# keyboard.net
KiCad netlist of a schematic drawn in Altium Designer
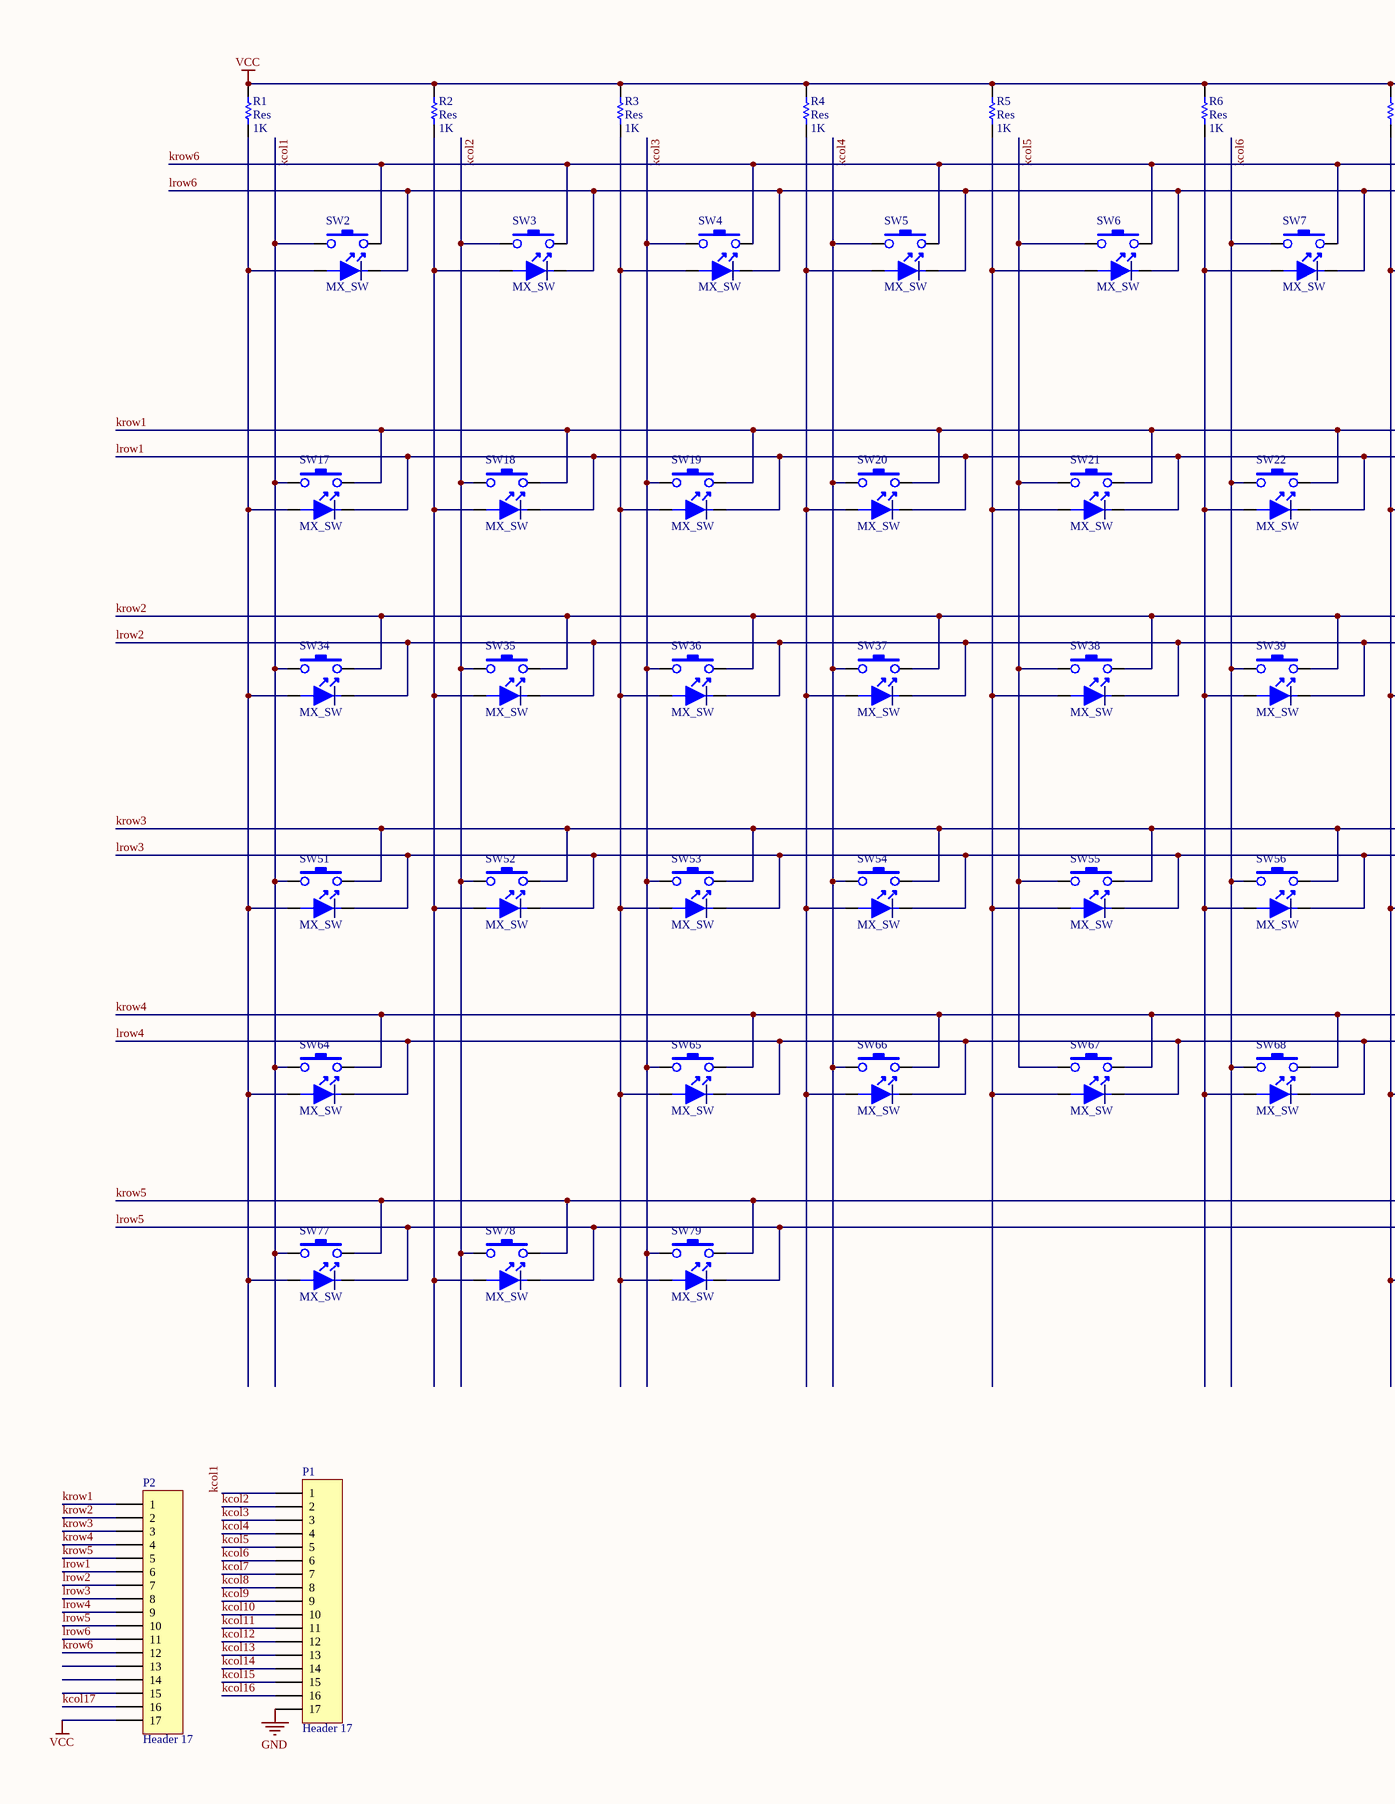
[diagram p0: keyboard.SchDoc, left]
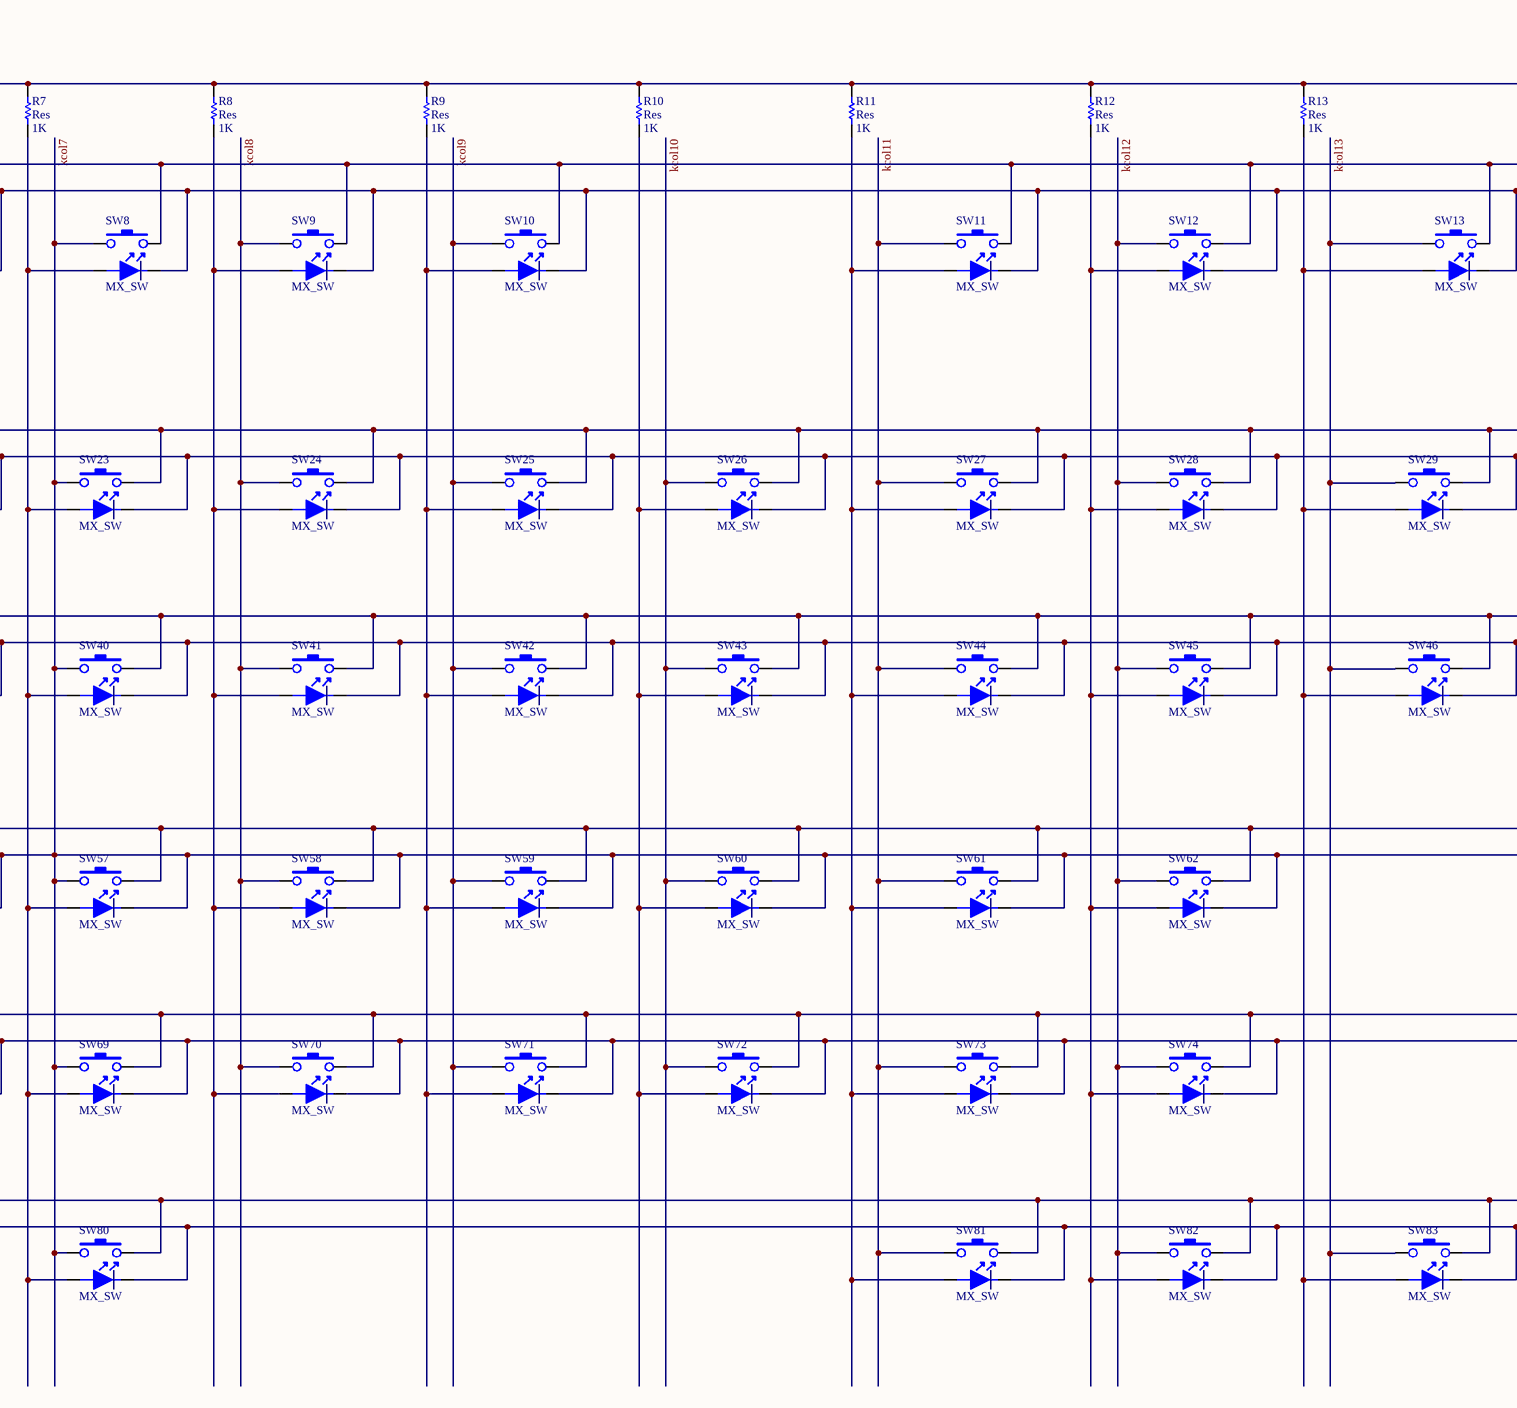
[diagram p1: keyboard.SchDoc, middle]
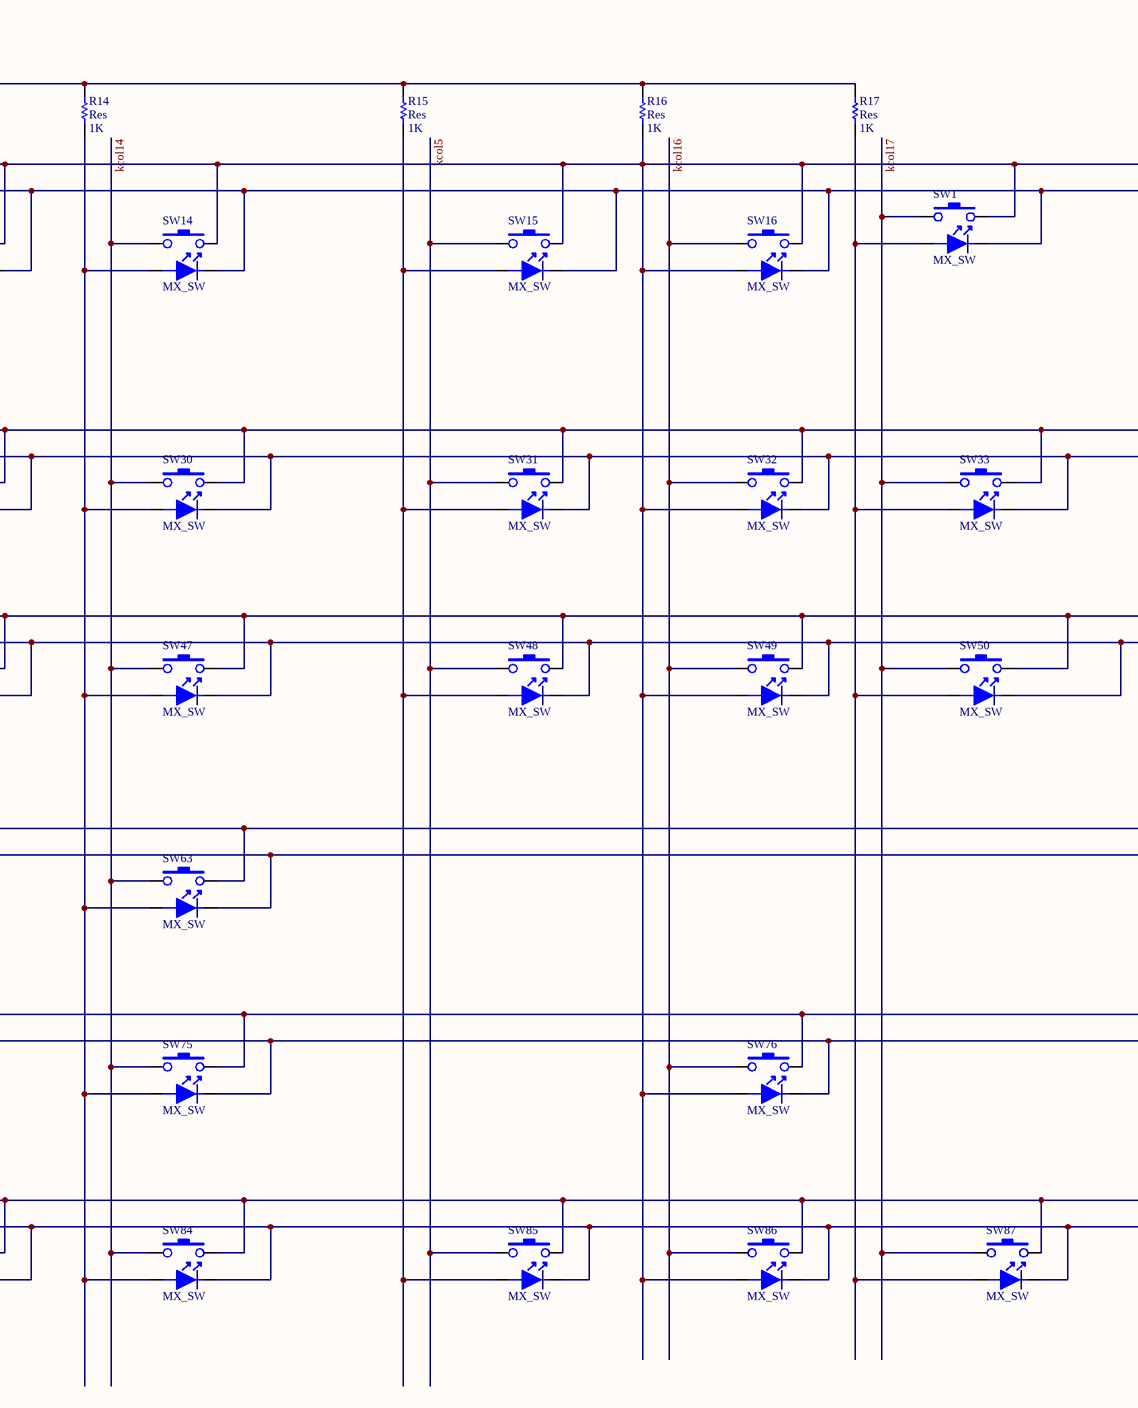
[diagram p2: keyboard.SchDoc, right]

(export (version "E")
  (design (tool "Eeschema 10.0.6"))
  (components
    (comp (ref "P1")
      (value "Header 17")
      (footprint "HDR1X17")
      (description "Header, 17-Pin")
      (fields (field (name "PUBLISHER") "Altium Limited"))
      (libsource (lib "常用元件集成库") (part "Header 17"))
    )
    (comp (ref "P2")
      (value "Header 17")
      (footprint "HDR1X17")
      (description "Header, 17-Pin")
      (fields (field (name "PUBLISHER") "Altium Limited"))
      (libsource (lib "常用元件集成库") (part "Header 17"))
    )
    (comp (ref "R1")
      (value "Res")
      (footprint "R2012")
      (description "贴片电阻")
      (fields (field (name "ALTIUM_VALUE") "1K") (field (name "PUBLISHER") "Altium Limited"))
      (libsource (lib "常用元件集成库") (part "Res"))
    )
    (comp (ref "R2")
      (value "Res")
      (footprint "R2012")
      (description "贴片电阻")
      (fields (field (name "ALTIUM_VALUE") "1K") (field (name "PUBLISHER") "Altium Limited"))
      (libsource (lib "常用元件集成库") (part "Res"))
    )
    (comp (ref "R3")
      (value "Res")
      (footprint "R2012")
      (description "贴片电阻")
      (fields (field (name "ALTIUM_VALUE") "1K") (field (name "PUBLISHER") "Altium Limited"))
      (libsource (lib "常用元件集成库") (part "Res"))
    )
    (comp (ref "R4")
      (value "Res")
      (footprint "R2012")
      (description "贴片电阻")
      (fields (field (name "ALTIUM_VALUE") "1K") (field (name "PUBLISHER") "Altium Limited"))
      (libsource (lib "常用元件集成库") (part "Res"))
    )
    (comp (ref "R5")
      (value "Res")
      (footprint "R2012")
      (description "贴片电阻")
      (fields (field (name "ALTIUM_VALUE") "1K") (field (name "PUBLISHER") "Altium Limited"))
      (libsource (lib "常用元件集成库") (part "Res"))
    )
    (comp (ref "R6")
      (value "Res")
      (footprint "R2012")
      (description "贴片电阻")
      (fields (field (name "ALTIUM_VALUE") "1K") (field (name "PUBLISHER") "Altium Limited"))
      (libsource (lib "常用元件集成库") (part "Res"))
    )
    (comp (ref "R7")
      (value "Res")
      (footprint "R2012")
      (description "贴片电阻")
      (fields (field (name "ALTIUM_VALUE") "1K") (field (name "PUBLISHER") "Altium Limited"))
      (libsource (lib "常用元件集成库") (part "Res"))
    )
    (comp (ref "R8")
      (value "Res")
      (footprint "R2012")
      (description "贴片电阻")
      (fields (field (name "ALTIUM_VALUE") "1K") (field (name "PUBLISHER") "Altium Limited"))
      (libsource (lib "常用元件集成库") (part "Res"))
    )
    (comp (ref "R9")
      (value "Res")
      (footprint "R2012")
      (description "贴片电阻")
      (fields (field (name "ALTIUM_VALUE") "1K") (field (name "PUBLISHER") "Altium Limited"))
      (libsource (lib "常用元件集成库") (part "Res"))
    )
    (comp (ref "R10")
      (value "Res")
      (footprint "R2012")
      (description "贴片电阻")
      (fields (field (name "ALTIUM_VALUE") "1K") (field (name "PUBLISHER") "Altium Limited"))
      (libsource (lib "常用元件集成库") (part "Res"))
    )
    (comp (ref "R11")
      (value "Res")
      (footprint "R2012")
      (description "贴片电阻")
      (fields (field (name "ALTIUM_VALUE") "1K") (field (name "PUBLISHER") "Altium Limited"))
      (libsource (lib "常用元件集成库") (part "Res"))
    )
    (comp (ref "R12")
      (value "Res")
      (footprint "R2012")
      (description "贴片电阻")
      (fields (field (name "ALTIUM_VALUE") "1K") (field (name "PUBLISHER") "Altium Limited"))
      (libsource (lib "常用元件集成库") (part "Res"))
    )
    (comp (ref "R13")
      (value "Res")
      (footprint "R2012")
      (description "贴片电阻")
      (fields (field (name "ALTIUM_VALUE") "1K") (field (name "PUBLISHER") "Altium Limited"))
      (libsource (lib "常用元件集成库") (part "Res"))
    )
    (comp (ref "R14")
      (value "Res")
      (footprint "R2012")
      (description "贴片电阻")
      (fields (field (name "ALTIUM_VALUE") "1K") (field (name "PUBLISHER") "Altium Limited"))
      (libsource (lib "常用元件集成库") (part "Res"))
    )
    (comp (ref "R15")
      (value "Res")
      (footprint "R2012")
      (description "贴片电阻")
      (fields (field (name "ALTIUM_VALUE") "1K") (field (name "PUBLISHER") "Altium Limited"))
      (libsource (lib "常用元件集成库") (part "Res"))
    )
    (comp (ref "R16")
      (value "Res")
      (footprint "R2012")
      (description "贴片电阻")
      (fields (field (name "ALTIUM_VALUE") "1K") (field (name "PUBLISHER") "Altium Limited"))
      (libsource (lib "常用元件集成库") (part "Res"))
    )
    (comp (ref "R17")
      (value "Res")
      (footprint "R2012")
      (description "贴片电阻")
      (fields (field (name "ALTIUM_VALUE") "1K") (field (name "PUBLISHER") "Altium Limited"))
      (libsource (lib "常用元件集成库") (part "Res"))
    )
    (comp (ref "SW1")
      (value "MX_SW")
      (footprint "MX_SW-2")
      (description "without Fixation pins  1-Pole w/LED")
      (libsource (lib "KeyBoard") (part "MX_SW-2"))
    )
    (comp (ref "SW2")
      (value "MX_SW")
      (footprint "MX_SW-2")
      (description "without Fixation pins  1-Pole w/LED")
      (libsource (lib "KeyBoard") (part "MX_SW-2"))
    )
    (comp (ref "SW3")
      (value "MX_SW")
      (footprint "MX_SW-2")
      (description "without Fixation pins  1-Pole w/LED")
      (libsource (lib "KeyBoard") (part "MX_SW-2"))
    )
    (comp (ref "SW4")
      (value "MX_SW")
      (footprint "MX_SW-2")
      (description "without Fixation pins  1-Pole w/LED")
      (libsource (lib "KeyBoard") (part "MX_SW-2"))
    )
    (comp (ref "SW5")
      (value "MX_SW")
      (footprint "MX_SW-2")
      (description "without Fixation pins  1-Pole w/LED")
      (libsource (lib "KeyBoard") (part "MX_SW-2"))
    )
    (comp (ref "SW6")
      (value "MX_SW")
      (footprint "MX_SW-2")
      (description "without Fixation pins  1-Pole w/LED")
      (libsource (lib "KeyBoard") (part "MX_SW-2"))
    )
    (comp (ref "SW7")
      (value "MX_SW")
      (footprint "MX_SW-2")
      (description "without Fixation pins  1-Pole w/LED")
      (libsource (lib "KeyBoard") (part "MX_SW-2"))
    )
    (comp (ref "SW8")
      (value "MX_SW")
      (footprint "MX_SW-2")
      (description "without Fixation pins  1-Pole w/LED")
      (libsource (lib "KeyBoard") (part "MX_SW-2"))
    )
    (comp (ref "SW9")
      (value "MX_SW")
      (footprint "MX_SW-2")
      (description "without Fixation pins  1-Pole w/LED")
      (libsource (lib "KeyBoard") (part "MX_SW-2"))
    )
    (comp (ref "SW10")
      (value "MX_SW")
      (footprint "MX_SW-2")
      (description "without Fixation pins  1-Pole w/LED")
      (libsource (lib "KeyBoard") (part "MX_SW-2"))
    )
    (comp (ref "SW11")
      (value "MX_SW")
      (footprint "MX_SW-2")
      (description "without Fixation pins  1-Pole w/LED")
      (libsource (lib "KeyBoard") (part "MX_SW-2"))
    )
    (comp (ref "SW12")
      (value "MX_SW")
      (footprint "MX_SW-2")
      (description "without Fixation pins  1-Pole w/LED")
      (libsource (lib "KeyBoard") (part "MX_SW-2"))
    )
    (comp (ref "SW13")
      (value "MX_SW")
      (footprint "MX_SW-2")
      (description "without Fixation pins  1-Pole w/LED")
      (libsource (lib "KeyBoard") (part "MX_SW-2"))
    )
    (comp (ref "SW14")
      (value "MX_SW")
      (footprint "MX_SW-2")
      (description "without Fixation pins  1-Pole w/LED")
      (libsource (lib "KeyBoard") (part "MX_SW-2"))
    )
    (comp (ref "SW15")
      (value "MX_SW")
      (footprint "MX_SW-2")
      (description "without Fixation pins  1-Pole w/LED")
      (libsource (lib "KeyBoard") (part "MX_SW-2"))
    )
    (comp (ref "SW16")
      (value "MX_SW")
      (footprint "MX_SW-2")
      (description "without Fixation pins  1-Pole w/LED")
      (libsource (lib "KeyBoard") (part "MX_SW-2"))
    )
    (comp (ref "SW17")
      (value "MX_SW")
      (footprint "MX_SW-2")
      (description "without Fixation pins  1-Pole w/LED")
      (libsource (lib "KeyBoard") (part "MX_SW-2"))
    )
    (comp (ref "SW18")
      (value "MX_SW")
      (footprint "MX_SW-2")
      (description "without Fixation pins  1-Pole w/LED")
      (libsource (lib "KeyBoard") (part "MX_SW-2"))
    )
    (comp (ref "SW19")
      (value "MX_SW")
      (footprint "MX_SW-2")
      (description "without Fixation pins  1-Pole w/LED")
      (libsource (lib "KeyBoard") (part "MX_SW-2"))
    )
    (comp (ref "SW20")
      (value "MX_SW")
      (footprint "MX_SW-2")
      (description "without Fixation pins  1-Pole w/LED")
      (libsource (lib "KeyBoard") (part "MX_SW-2"))
    )
    (comp (ref "SW21")
      (value "MX_SW")
      (footprint "MX_SW-2")
      (description "without Fixation pins  1-Pole w/LED")
      (libsource (lib "KeyBoard") (part "MX_SW-2"))
    )
    (comp (ref "SW22")
      (value "MX_SW")
      (footprint "MX_SW-2")
      (description "without Fixation pins  1-Pole w/LED")
      (libsource (lib "KeyBoard") (part "MX_SW-2"))
    )
    (comp (ref "SW23")
      (value "MX_SW")
      (footprint "MX_SW-2")
      (description "without Fixation pins  1-Pole w/LED")
      (libsource (lib "KeyBoard") (part "MX_SW-2"))
    )
    (comp (ref "SW24")
      (value "MX_SW")
      (footprint "MX_SW-2")
      (description "without Fixation pins  1-Pole w/LED")
      (libsource (lib "KeyBoard") (part "MX_SW-2"))
    )
    (comp (ref "SW25")
      (value "MX_SW")
      (footprint "MX_SW-2")
      (description "without Fixation pins  1-Pole w/LED")
      (libsource (lib "KeyBoard") (part "MX_SW-2"))
    )
    (comp (ref "SW26")
      (value "MX_SW")
      (footprint "MX_SW-2")
      (description "without Fixation pins  1-Pole w/LED")
      (libsource (lib "KeyBoard") (part "MX_SW-2"))
    )
    (comp (ref "SW27")
      (value "MX_SW")
      (footprint "MX_SW-2")
      (description "without Fixation pins  1-Pole w/LED")
      (libsource (lib "KeyBoard") (part "MX_SW-2"))
    )
    (comp (ref "SW28")
      (value "MX_SW")
      (footprint "MX_SW-2")
      (description "without Fixation pins  1-Pole w/LED")
      (libsource (lib "KeyBoard") (part "MX_SW-2"))
    )
    (comp (ref "SW29")
      (value "MX_SW")
      (footprint "MX_SW-2")
      (description "without Fixation pins  1-Pole w/LED")
      (libsource (lib "KeyBoard") (part "MX_SW-2"))
    )
    (comp (ref "SW30")
      (value "MX_SW")
      (footprint "MX_SW-2")
      (description "without Fixation pins  1-Pole w/LED")
      (libsource (lib "KeyBoard") (part "MX_SW-2"))
    )
    (comp (ref "SW31")
      (value "MX_SW")
      (footprint "MX_SW-2")
      (description "without Fixation pins  1-Pole w/LED")
      (libsource (lib "KeyBoard") (part "MX_SW-2"))
    )
    (comp (ref "SW32")
      (value "MX_SW")
      (footprint "MX_SW-2")
      (description "without Fixation pins  1-Pole w/LED")
      (libsource (lib "KeyBoard") (part "MX_SW-2"))
    )
    (comp (ref "SW33")
      (value "MX_SW")
      (footprint "MX_SW-2")
      (description "without Fixation pins  1-Pole w/LED")
      (libsource (lib "KeyBoard") (part "MX_SW-2"))
    )
    (comp (ref "SW34")
      (value "MX_SW")
      (footprint "MX_SW-2")
      (description "without Fixation pins  1-Pole w/LED")
      (libsource (lib "KeyBoard") (part "MX_SW-2"))
    )
    (comp (ref "SW35")
      (value "MX_SW")
      (footprint "MX_SW-2")
      (description "without Fixation pins  1-Pole w/LED")
      (libsource (lib "KeyBoard") (part "MX_SW-2"))
    )
    (comp (ref "SW36")
      (value "MX_SW")
      (footprint "MX_SW-2")
      (description "without Fixation pins  1-Pole w/LED")
      (libsource (lib "KeyBoard") (part "MX_SW-2"))
    )
    (comp (ref "SW37")
      (value "MX_SW")
      (footprint "MX_SW-2")
      (description "without Fixation pins  1-Pole w/LED")
      (libsource (lib "KeyBoard") (part "MX_SW-2"))
    )
    (comp (ref "SW38")
      (value "MX_SW")
      (footprint "MX_SW-2")
      (description "without Fixation pins  1-Pole w/LED")
      (libsource (lib "KeyBoard") (part "MX_SW-2"))
    )
    (comp (ref "SW39")
      (value "MX_SW")
      (footprint "MX_SW-2")
      (description "without Fixation pins  1-Pole w/LED")
      (libsource (lib "KeyBoard") (part "MX_SW-2"))
    )
    (comp (ref "SW40")
      (value "MX_SW")
      (footprint "MX_SW-2")
      (description "without Fixation pins  1-Pole w/LED")
      (libsource (lib "KeyBoard") (part "MX_SW-2"))
    )
    (comp (ref "SW41")
      (value "MX_SW")
      (footprint "MX_SW-2")
      (description "without Fixation pins  1-Pole w/LED")
      (libsource (lib "KeyBoard") (part "MX_SW-2"))
    )
    (comp (ref "SW42")
      (value "MX_SW")
      (footprint "MX_SW-2")
      (description "without Fixation pins  1-Pole w/LED")
      (libsource (lib "KeyBoard") (part "MX_SW-2"))
    )
    (comp (ref "SW43")
      (value "MX_SW")
      (footprint "MX_SW-2")
      (description "without Fixation pins  1-Pole w/LED")
      (libsource (lib "KeyBoard") (part "MX_SW-2"))
    )
    (comp (ref "SW44")
      (value "MX_SW")
      (footprint "MX_SW-2")
      (description "without Fixation pins  1-Pole w/LED")
      (libsource (lib "KeyBoard") (part "MX_SW-2"))
    )
    (comp (ref "SW45")
      (value "MX_SW")
      (footprint "MX_SW-2")
      (description "without Fixation pins  1-Pole w/LED")
      (libsource (lib "KeyBoard") (part "MX_SW-2"))
    )
    (comp (ref "SW46")
      (value "MX_SW")
      (footprint "MX_SW-2")
      (description "without Fixation pins  1-Pole w/LED")
      (libsource (lib "KeyBoard") (part "MX_SW-2"))
    )
    (comp (ref "SW47")
      (value "MX_SW")
      (footprint "MX_SW-2")
      (description "without Fixation pins  1-Pole w/LED")
      (libsource (lib "KeyBoard") (part "MX_SW-2"))
    )
    (comp (ref "SW48")
      (value "MX_SW")
      (footprint "MX_SW-2")
      (description "without Fixation pins  1-Pole w/LED")
      (libsource (lib "KeyBoard") (part "MX_SW-2"))
    )
    (comp (ref "SW49")
      (value "MX_SW")
      (footprint "MX_SW-2")
      (description "without Fixation pins  1-Pole w/LED")
      (libsource (lib "KeyBoard") (part "MX_SW-2"))
    )
    (comp (ref "SW50")
      (value "MX_SW")
      (footprint "MX_SW-2")
      (description "without Fixation pins  1-Pole w/LED")
      (libsource (lib "KeyBoard") (part "MX_SW-2"))
    )
    (comp (ref "SW51")
      (value "MX_SW")
      (footprint "MX_SW-2")
      (description "without Fixation pins  1-Pole w/LED")
      (libsource (lib "KeyBoard") (part "MX_SW-2"))
    )
    (comp (ref "SW52")
      (value "MX_SW")
      (footprint "MX_SW-2")
      (description "without Fixation pins  1-Pole w/LED")
      (libsource (lib "KeyBoard") (part "MX_SW-2"))
    )
    (comp (ref "SW53")
      (value "MX_SW")
      (footprint "MX_SW-2")
      (description "without Fixation pins  1-Pole w/LED")
      (libsource (lib "KeyBoard") (part "MX_SW-2"))
    )
    (comp (ref "SW54")
      (value "MX_SW")
      (footprint "MX_SW-2")
      (description "without Fixation pins  1-Pole w/LED")
      (libsource (lib "KeyBoard") (part "MX_SW-2"))
    )
    (comp (ref "SW55")
      (value "MX_SW")
      (footprint "MX_SW-2")
      (description "without Fixation pins  1-Pole w/LED")
      (libsource (lib "KeyBoard") (part "MX_SW-2"))
    )
    (comp (ref "SW56")
      (value "MX_SW")
      (footprint "MX_SW-2")
      (description "without Fixation pins  1-Pole w/LED")
      (libsource (lib "KeyBoard") (part "MX_SW-2"))
    )
    (comp (ref "SW57")
      (value "MX_SW")
      (footprint "MX_SW-2")
      (description "without Fixation pins  1-Pole w/LED")
      (libsource (lib "KeyBoard") (part "MX_SW-2"))
    )
    (comp (ref "SW58")
      (value "MX_SW")
      (footprint "MX_SW-2")
      (description "without Fixation pins  1-Pole w/LED")
      (libsource (lib "KeyBoard") (part "MX_SW-2"))
    )
    (comp (ref "SW59")
      (value "MX_SW")
      (footprint "MX_SW-2")
      (description "without Fixation pins  1-Pole w/LED")
      (libsource (lib "KeyBoard") (part "MX_SW-2"))
    )
    (comp (ref "SW60")
      (value "MX_SW")
      (footprint "MX_SW-2")
      (description "without Fixation pins  1-Pole w/LED")
      (libsource (lib "KeyBoard") (part "MX_SW-2"))
    )
    (comp (ref "SW61")
      (value "MX_SW")
      (footprint "MX_SW-2")
      (description "without Fixation pins  1-Pole w/LED")
      (libsource (lib "KeyBoard") (part "MX_SW-2"))
    )
    (comp (ref "SW62")
      (value "MX_SW")
      (footprint "MX_SW-2")
      (description "without Fixation pins  1-Pole w/LED")
      (libsource (lib "KeyBoard") (part "MX_SW-2"))
    )
    (comp (ref "SW63")
      (value "MX_SW")
      (footprint "MX_SW-2")
      (description "without Fixation pins  1-Pole w/LED")
      (libsource (lib "KeyBoard") (part "MX_SW-2"))
    )
    (comp (ref "SW64")
      (value "MX_SW")
      (footprint "MX_SW-2")
      (description "without Fixation pins  1-Pole w/LED")
      (libsource (lib "KeyBoard") (part "MX_SW-2"))
    )
    (comp (ref "SW65")
      (value "MX_SW")
      (footprint "MX_SW-2")
      (description "without Fixation pins  1-Pole w/LED")
      (libsource (lib "KeyBoard") (part "MX_SW-2"))
    )
    (comp (ref "SW66")
      (value "MX_SW")
      (footprint "MX_SW-2")
      (description "without Fixation pins  1-Pole w/LED")
      (libsource (lib "KeyBoard") (part "MX_SW-2"))
    )
    (comp (ref "SW67")
      (value "MX_SW")
      (footprint "MX_SW-2")
      (description "without Fixation pins  1-Pole w/LED")
      (libsource (lib "KeyBoard") (part "MX_SW-2"))
    )
    (comp (ref "SW68")
      (value "MX_SW")
      (footprint "MX_SW-2")
      (description "without Fixation pins  1-Pole w/LED")
      (libsource (lib "KeyBoard") (part "MX_SW-2"))
    )
    (comp (ref "SW69")
      (value "MX_SW")
      (footprint "MX_SW-2")
      (description "without Fixation pins  1-Pole w/LED")
      (libsource (lib "KeyBoard") (part "MX_SW-2"))
    )
    (comp (ref "SW70")
      (value "MX_SW")
      (footprint "MX_SW-2")
      (description "without Fixation pins  1-Pole w/LED")
      (libsource (lib "KeyBoard") (part "MX_SW-2"))
    )
    (comp (ref "SW71")
      (value "MX_SW")
      (footprint "MX_SW-2")
      (description "without Fixation pins  1-Pole w/LED")
      (libsource (lib "KeyBoard") (part "MX_SW-2"))
    )
    (comp (ref "SW72")
      (value "MX_SW")
      (footprint "MX_SW-2")
      (description "without Fixation pins  1-Pole w/LED")
      (libsource (lib "KeyBoard") (part "MX_SW-2"))
    )
    (comp (ref "SW73")
      (value "MX_SW")
      (footprint "MX_SW-2")
      (description "without Fixation pins  1-Pole w/LED")
      (libsource (lib "KeyBoard") (part "MX_SW-2"))
    )
    (comp (ref "SW74")
      (value "MX_SW")
      (footprint "MX_SW-2")
      (description "without Fixation pins  1-Pole w/LED")
      (libsource (lib "KeyBoard") (part "MX_SW-2"))
    )
    (comp (ref "SW75")
      (value "MX_SW")
      (footprint "MX_SW-2")
      (description "without Fixation pins  1-Pole w/LED")
      (libsource (lib "KeyBoard") (part "MX_SW-2"))
    )
    (comp (ref "SW76")
      (value "MX_SW")
      (footprint "MX_SW-2")
      (description "without Fixation pins  1-Pole w/LED")
      (libsource (lib "KeyBoard") (part "MX_SW-2"))
    )
    (comp (ref "SW77")
      (value "MX_SW")
      (footprint "MX_SW-2")
      (description "without Fixation pins  1-Pole w/LED")
      (libsource (lib "KeyBoard") (part "MX_SW-2"))
    )
    (comp (ref "SW78")
      (value "MX_SW")
      (footprint "MX_SW-2")
      (description "without Fixation pins  1-Pole w/LED")
      (libsource (lib "KeyBoard") (part "MX_SW-2"))
    )
    (comp (ref "SW79")
      (value "MX_SW")
      (footprint "MX_SW-2")
      (description "without Fixation pins  1-Pole w/LED")
      (libsource (lib "KeyBoard") (part "MX_SW-2"))
    )
    (comp (ref "SW80")
      (value "MX_SW")
      (footprint "MX_SW-2")
      (description "without Fixation pins  1-Pole w/LED")
      (libsource (lib "KeyBoard") (part "MX_SW-2"))
    )
    (comp (ref "SW81")
      (value "MX_SW")
      (footprint "MX_SW-2")
      (description "without Fixation pins  1-Pole w/LED")
      (libsource (lib "KeyBoard") (part "MX_SW-2"))
    )
    (comp (ref "SW82")
      (value "MX_SW")
      (footprint "MX_SW-2")
      (description "without Fixation pins  1-Pole w/LED")
      (libsource (lib "KeyBoard") (part "MX_SW-2"))
    )
    (comp (ref "SW83")
      (value "MX_SW")
      (footprint "MX_SW-2")
      (description "without Fixation pins  1-Pole w/LED")
      (libsource (lib "KeyBoard") (part "MX_SW-2"))
    )
    (comp (ref "SW84")
      (value "MX_SW")
      (footprint "MX_SW-2")
      (description "without Fixation pins  1-Pole w/LED")
      (libsource (lib "KeyBoard") (part "MX_SW-2"))
    )
    (comp (ref "SW85")
      (value "MX_SW")
      (footprint "MX_SW-2")
      (description "without Fixation pins  1-Pole w/LED")
      (libsource (lib "KeyBoard") (part "MX_SW-2"))
    )
    (comp (ref "SW86")
      (value "MX_SW")
      (footprint "MX_SW-2")
      (description "without Fixation pins  1-Pole w/LED")
      (libsource (lib "KeyBoard") (part "MX_SW-2"))
    )
    (comp (ref "SW87")
      (value "MX_SW")
      (footprint "MX_SW-2")
      (description "without Fixation pins  1-Pole w/LED")
      (libsource (lib "KeyBoard") (part "MX_SW-2"))
    )
  )
  (nets
    (net (code "1") (name "/kcol1") (class "Default")
      (node (ref "P1") (pin "1") (pinfunction "1_1") (pintype "passive"))
      (node (ref "SW17") (pin "1") (pinfunction "1_1") (pintype "passive"))
      (node (ref "SW2") (pin "1") (pinfunction "1_1") (pintype "passive"))
      (node (ref "SW34") (pin "1") (pinfunction "1_1") (pintype "passive"))
      (node (ref "SW51") (pin "1") (pinfunction "1_1") (pintype "passive"))
      (node (ref "SW64") (pin "1") (pinfunction "1_1") (pintype "passive"))
      (node (ref "SW77") (pin "1") (pinfunction "1_1") (pintype "passive"))
    )
    (net (code "2") (name "/kcol2") (class "Default")
      (node (ref "P1") (pin "2") (pinfunction "2_2") (pintype "passive"))
      (node (ref "SW18") (pin "1") (pinfunction "1_1") (pintype "passive"))
      (node (ref "SW3") (pin "1") (pinfunction "1_1") (pintype "passive"))
      (node (ref "SW35") (pin "1") (pinfunction "1_1") (pintype "passive"))
      (node (ref "SW52") (pin "1") (pinfunction "1_1") (pintype "passive"))
      (node (ref "SW78") (pin "1") (pinfunction "1_1") (pintype "passive"))
    )
    (net (code "3") (name "/kcol3") (class "Default")
      (node (ref "P1") (pin "3") (pinfunction "3_3") (pintype "passive"))
      (node (ref "SW19") (pin "1") (pinfunction "1_1") (pintype "passive"))
      (node (ref "SW36") (pin "1") (pinfunction "1_1") (pintype "passive"))
      (node (ref "SW4") (pin "1") (pinfunction "1_1") (pintype "passive"))
      (node (ref "SW53") (pin "1") (pinfunction "1_1") (pintype "passive"))
      (node (ref "SW65") (pin "1") (pinfunction "1_1") (pintype "passive"))
      (node (ref "SW79") (pin "1") (pinfunction "1_1") (pintype "passive"))
    )
    (net (code "4") (name "/kcol4") (class "Default")
      (node (ref "P1") (pin "4") (pinfunction "4_4") (pintype "passive"))
      (node (ref "SW20") (pin "1") (pinfunction "1_1") (pintype "passive"))
      (node (ref "SW37") (pin "1") (pinfunction "1_1") (pintype "passive"))
      (node (ref "SW5") (pin "1") (pinfunction "1_1") (pintype "passive"))
      (node (ref "SW54") (pin "1") (pinfunction "1_1") (pintype "passive"))
      (node (ref "SW66") (pin "1") (pinfunction "1_1") (pintype "passive"))
    )
    (net (code "5") (name "/kcol5") (class "Default")
      (node (ref "P1") (pin "5") (pinfunction "5_5") (pintype "passive"))
      (node (ref "SW15") (pin "1") (pinfunction "1_1") (pintype "passive"))
      (node (ref "SW21") (pin "1") (pinfunction "1_1") (pintype "passive"))
      (node (ref "SW31") (pin "1") (pinfunction "1_1") (pintype "passive"))
      (node (ref "SW38") (pin "1") (pinfunction "1_1") (pintype "passive"))
      (node (ref "SW48") (pin "1") (pinfunction "1_1") (pintype "passive"))
      (node (ref "SW55") (pin "1") (pinfunction "1_1") (pintype "passive"))
      (node (ref "SW6") (pin "1") (pinfunction "1_1") (pintype "passive"))
      (node (ref "SW67") (pin "1") (pinfunction "1_1") (pintype "passive"))
      (node (ref "SW85") (pin "1") (pinfunction "1_1") (pintype "passive"))
    )
    (net (code "6") (name "/kcol6") (class "Default")
      (node (ref "P1") (pin "6") (pinfunction "6_6") (pintype "passive"))
      (node (ref "SW22") (pin "1") (pinfunction "1_1") (pintype "passive"))
      (node (ref "SW39") (pin "1") (pinfunction "1_1") (pintype "passive"))
      (node (ref "SW56") (pin "1") (pinfunction "1_1") (pintype "passive"))
      (node (ref "SW68") (pin "1") (pinfunction "1_1") (pintype "passive"))
      (node (ref "SW7") (pin "1") (pinfunction "1_1") (pintype "passive"))
    )
    (net (code "7") (name "/kcol7") (class "Default")
      (node (ref "P1") (pin "7") (pinfunction "7_7") (pintype "passive"))
      (node (ref "P2") (pin "8") (pinfunction "8_8") (pintype "passive"))
      (node (ref "SW23") (pin "1") (pinfunction "1_1") (pintype "passive"))
      (node (ref "SW40") (pin "1") (pinfunction "1_1") (pintype "passive"))
      (node (ref "SW51") (pin "4") (pinfunction "4_4") (pintype "passive"))
      (node (ref "SW52") (pin "4") (pinfunction "4_4") (pintype "passive"))
      (node (ref "SW53") (pin "4") (pinfunction "4_4") (pintype "passive"))
      (node (ref "SW54") (pin "4") (pinfunction "4_4") (pintype "passive"))
      (node (ref "SW55") (pin "4") (pinfunction "4_4") (pintype "passive"))
      (node (ref "SW56") (pin "4") (pinfunction "4_4") (pintype "passive"))
      (node (ref "SW57") (pin "1") (pinfunction "1_1") (pintype "passive"))
      (node (ref "SW57") (pin "4") (pinfunction "4_4") (pintype "passive"))
      (node (ref "SW58") (pin "4") (pinfunction "4_4") (pintype "passive"))
      (node (ref "SW59") (pin "4") (pinfunction "4_4") (pintype "passive"))
      (node (ref "SW60") (pin "4") (pinfunction "4_4") (pintype "passive"))
      (node (ref "SW61") (pin "4") (pinfunction "4_4") (pintype "passive"))
      (node (ref "SW62") (pin "4") (pinfunction "4_4") (pintype "passive"))
      (node (ref "SW63") (pin "4") (pinfunction "4_4") (pintype "passive"))
      (node (ref "SW69") (pin "1") (pinfunction "1_1") (pintype "passive"))
      (node (ref "SW8") (pin "1") (pinfunction "1_1") (pintype "passive"))
      (node (ref "SW80") (pin "1") (pinfunction "1_1") (pintype "passive"))
    )
    (net (code "8") (name "/kcol8") (class "Default")
      (node (ref "P1") (pin "8") (pinfunction "8_8") (pintype "passive"))
      (node (ref "SW24") (pin "1") (pinfunction "1_1") (pintype "passive"))
      (node (ref "SW41") (pin "1") (pinfunction "1_1") (pintype "passive"))
      (node (ref "SW58") (pin "1") (pinfunction "1_1") (pintype "passive"))
      (node (ref "SW70") (pin "1") (pinfunction "1_1") (pintype "passive"))
      (node (ref "SW9") (pin "1") (pinfunction "1_1") (pintype "passive"))
    )
    (net (code "9") (name "/kcol9") (class "Default")
      (node (ref "P1") (pin "9") (pinfunction "9_9") (pintype "passive"))
      (node (ref "SW10") (pin "1") (pinfunction "1_1") (pintype "passive"))
      (node (ref "SW25") (pin "1") (pinfunction "1_1") (pintype "passive"))
      (node (ref "SW42") (pin "1") (pinfunction "1_1") (pintype "passive"))
      (node (ref "SW59") (pin "1") (pinfunction "1_1") (pintype "passive"))
      (node (ref "SW71") (pin "1") (pinfunction "1_1") (pintype "passive"))
    )
    (net (code "10") (name "/kcol10") (class "Default")
      (node (ref "P1") (pin "10") (pinfunction "10_10") (pintype "passive"))
      (node (ref "SW26") (pin "1") (pinfunction "1_1") (pintype "passive"))
      (node (ref "SW43") (pin "1") (pinfunction "1_1") (pintype "passive"))
      (node (ref "SW60") (pin "1") (pinfunction "1_1") (pintype "passive"))
      (node (ref "SW72") (pin "1") (pinfunction "1_1") (pintype "passive"))
    )
    (net (code "11") (name "/kcol11") (class "Default")
      (node (ref "P1") (pin "11") (pinfunction "11_11") (pintype "passive"))
      (node (ref "SW11") (pin "1") (pinfunction "1_1") (pintype "passive"))
      (node (ref "SW27") (pin "1") (pinfunction "1_1") (pintype "passive"))
      (node (ref "SW44") (pin "1") (pinfunction "1_1") (pintype "passive"))
      (node (ref "SW61") (pin "1") (pinfunction "1_1") (pintype "passive"))
      (node (ref "SW73") (pin "1") (pinfunction "1_1") (pintype "passive"))
      (node (ref "SW81") (pin "1") (pinfunction "1_1") (pintype "passive"))
    )
    (net (code "12") (name "/kcol12") (class "Default")
      (node (ref "P1") (pin "12") (pinfunction "12_12") (pintype "passive"))
      (node (ref "SW12") (pin "1") (pinfunction "1_1") (pintype "passive"))
      (node (ref "SW28") (pin "1") (pinfunction "1_1") (pintype "passive"))
      (node (ref "SW45") (pin "1") (pinfunction "1_1") (pintype "passive"))
      (node (ref "SW62") (pin "1") (pinfunction "1_1") (pintype "passive"))
      (node (ref "SW74") (pin "1") (pinfunction "1_1") (pintype "passive"))
      (node (ref "SW82") (pin "1") (pinfunction "1_1") (pintype "passive"))
    )
    (net (code "13") (name "/kcol13") (class "Default")
      (node (ref "P1") (pin "13") (pinfunction "13_13") (pintype "passive"))
      (node (ref "SW13") (pin "1") (pinfunction "1_1") (pintype "passive"))
      (node (ref "SW29") (pin "1") (pinfunction "1_1") (pintype "passive"))
      (node (ref "SW46") (pin "1") (pinfunction "1_1") (pintype "passive"))
      (node (ref "SW83") (pin "1") (pinfunction "1_1") (pintype "passive"))
    )
    (net (code "14") (name "/kcol14") (class "Default")
      (node (ref "P1") (pin "14") (pinfunction "14_14") (pintype "passive"))
      (node (ref "SW14") (pin "1") (pinfunction "1_1") (pintype "passive"))
      (node (ref "SW30") (pin "1") (pinfunction "1_1") (pintype "passive"))
      (node (ref "SW47") (pin "1") (pinfunction "1_1") (pintype "passive"))
      (node (ref "SW63") (pin "1") (pinfunction "1_1") (pintype "passive"))
      (node (ref "SW75") (pin "1") (pinfunction "1_1") (pintype "passive"))
      (node (ref "SW84") (pin "1") (pinfunction "1_1") (pintype "passive"))
    )
    (net (code "15") (name "/kcol15") (class "Default")
      (node (ref "P1") (pin "15") (pinfunction "15_15") (pintype "passive"))
    )
    (net (code "16") (name "/kcol16") (class "Default")
      (node (ref "P1") (pin "16") (pinfunction "16_16") (pintype "passive"))
      (node (ref "SW16") (pin "1") (pinfunction "1_1") (pintype "passive"))
      (node (ref "SW32") (pin "1") (pinfunction "1_1") (pintype "passive"))
      (node (ref "SW49") (pin "1") (pinfunction "1_1") (pintype "passive"))
      (node (ref "SW76") (pin "1") (pinfunction "1_1") (pintype "passive"))
      (node (ref "SW86") (pin "1") (pinfunction "1_1") (pintype "passive"))
    )
    (net (code "17") (name "/kcol17") (class "Default")
      (node (ref "P2") (pin "16") (pinfunction "16_16") (pintype "passive"))
      (node (ref "SW1") (pin "1") (pinfunction "1_1") (pintype "passive"))
      (node (ref "SW33") (pin "1") (pinfunction "1_1") (pintype "passive"))
      (node (ref "SW50") (pin "1") (pinfunction "1_1") (pintype "passive"))
      (node (ref "SW87") (pin "1") (pinfunction "1_1") (pintype "passive"))
    )
    (net (code "18") (name "/krow1") (class "Default")
      (node (ref "P2") (pin "1") (pinfunction "1_1") (pintype "passive"))
      (node (ref "SW17") (pin "2") (pinfunction "2_2") (pintype "passive"))
      (node (ref "SW18") (pin "2") (pinfunction "2_2") (pintype "passive"))
      (node (ref "SW19") (pin "2") (pinfunction "2_2") (pintype "passive"))
      (node (ref "SW20") (pin "2") (pinfunction "2_2") (pintype "passive"))
      (node (ref "SW21") (pin "2") (pinfunction "2_2") (pintype "passive"))
      (node (ref "SW22") (pin "2") (pinfunction "2_2") (pintype "passive"))
      (node (ref "SW23") (pin "2") (pinfunction "2_2") (pintype "passive"))
      (node (ref "SW24") (pin "2") (pinfunction "2_2") (pintype "passive"))
      (node (ref "SW25") (pin "2") (pinfunction "2_2") (pintype "passive"))
      (node (ref "SW26") (pin "2") (pinfunction "2_2") (pintype "passive"))
      (node (ref "SW27") (pin "2") (pinfunction "2_2") (pintype "passive"))
      (node (ref "SW28") (pin "2") (pinfunction "2_2") (pintype "passive"))
      (node (ref "SW29") (pin "2") (pinfunction "2_2") (pintype "passive"))
      (node (ref "SW30") (pin "2") (pinfunction "2_2") (pintype "passive"))
      (node (ref "SW31") (pin "2") (pinfunction "2_2") (pintype "passive"))
      (node (ref "SW32") (pin "2") (pinfunction "2_2") (pintype "passive"))
      (node (ref "SW33") (pin "2") (pinfunction "2_2") (pintype "passive"))
    )
    (net (code "19") (name "/krow2") (class "Default")
      (node (ref "P2") (pin "2") (pinfunction "2_2") (pintype "passive"))
      (node (ref "SW34") (pin "2") (pinfunction "2_2") (pintype "passive"))
      (node (ref "SW35") (pin "2") (pinfunction "2_2") (pintype "passive"))
      (node (ref "SW36") (pin "2") (pinfunction "2_2") (pintype "passive"))
      (node (ref "SW37") (pin "2") (pinfunction "2_2") (pintype "passive"))
      (node (ref "SW38") (pin "2") (pinfunction "2_2") (pintype "passive"))
      (node (ref "SW39") (pin "2") (pinfunction "2_2") (pintype "passive"))
      (node (ref "SW40") (pin "2") (pinfunction "2_2") (pintype "passive"))
      (node (ref "SW41") (pin "2") (pinfunction "2_2") (pintype "passive"))
      (node (ref "SW42") (pin "2") (pinfunction "2_2") (pintype "passive"))
      (node (ref "SW43") (pin "2") (pinfunction "2_2") (pintype "passive"))
      (node (ref "SW44") (pin "2") (pinfunction "2_2") (pintype "passive"))
      (node (ref "SW45") (pin "2") (pinfunction "2_2") (pintype "passive"))
      (node (ref "SW46") (pin "2") (pinfunction "2_2") (pintype "passive"))
      (node (ref "SW47") (pin "2") (pinfunction "2_2") (pintype "passive"))
      (node (ref "SW48") (pin "2") (pinfunction "2_2") (pintype "passive"))
      (node (ref "SW49") (pin "2") (pinfunction "2_2") (pintype "passive"))
      (node (ref "SW50") (pin "2") (pinfunction "2_2") (pintype "passive"))
    )
    (net (code "20") (name "/krow3") (class "Default")
      (node (ref "P2") (pin "3") (pinfunction "3_3") (pintype "passive"))
      (node (ref "SW51") (pin "2") (pinfunction "2_2") (pintype "passive"))
      (node (ref "SW52") (pin "2") (pinfunction "2_2") (pintype "passive"))
      (node (ref "SW53") (pin "2") (pinfunction "2_2") (pintype "passive"))
      (node (ref "SW54") (pin "2") (pinfunction "2_2") (pintype "passive"))
      (node (ref "SW55") (pin "2") (pinfunction "2_2") (pintype "passive"))
      (node (ref "SW56") (pin "2") (pinfunction "2_2") (pintype "passive"))
      (node (ref "SW57") (pin "2") (pinfunction "2_2") (pintype "passive"))
      (node (ref "SW58") (pin "2") (pinfunction "2_2") (pintype "passive"))
      (node (ref "SW59") (pin "2") (pinfunction "2_2") (pintype "passive"))
      (node (ref "SW60") (pin "2") (pinfunction "2_2") (pintype "passive"))
      (node (ref "SW61") (pin "2") (pinfunction "2_2") (pintype "passive"))
      (node (ref "SW62") (pin "2") (pinfunction "2_2") (pintype "passive"))
      (node (ref "SW63") (pin "2") (pinfunction "2_2") (pintype "passive"))
    )
    (net (code "21") (name "/krow4") (class "Default")
      (node (ref "P2") (pin "4") (pinfunction "4_4") (pintype "passive"))
      (node (ref "SW64") (pin "2") (pinfunction "2_2") (pintype "passive"))
      (node (ref "SW65") (pin "2") (pinfunction "2_2") (pintype "passive"))
      (node (ref "SW66") (pin "2") (pinfunction "2_2") (pintype "passive"))
      (node (ref "SW67") (pin "2") (pinfunction "2_2") (pintype "passive"))
      (node (ref "SW68") (pin "2") (pinfunction "2_2") (pintype "passive"))
      (node (ref "SW69") (pin "2") (pinfunction "2_2") (pintype "passive"))
      (node (ref "SW70") (pin "2") (pinfunction "2_2") (pintype "passive"))
      (node (ref "SW71") (pin "2") (pinfunction "2_2") (pintype "passive"))
      (node (ref "SW72") (pin "2") (pinfunction "2_2") (pintype "passive"))
      (node (ref "SW73") (pin "2") (pinfunction "2_2") (pintype "passive"))
      (node (ref "SW74") (pin "2") (pinfunction "2_2") (pintype "passive"))
      (node (ref "SW75") (pin "2") (pinfunction "2_2") (pintype "passive"))
      (node (ref "SW76") (pin "2") (pinfunction "2_2") (pintype "passive"))
    )
    (net (code "22") (name "/krow5") (class "Default")
      (node (ref "P2") (pin "5") (pinfunction "5_5") (pintype "passive"))
      (node (ref "SW77") (pin "2") (pinfunction "2_2") (pintype "passive"))
      (node (ref "SW78") (pin "2") (pinfunction "2_2") (pintype "passive"))
      (node (ref "SW79") (pin "2") (pinfunction "2_2") (pintype "passive"))
      (node (ref "SW80") (pin "2") (pinfunction "2_2") (pintype "passive"))
      (node (ref "SW81") (pin "2") (pinfunction "2_2") (pintype "passive"))
      (node (ref "SW82") (pin "2") (pinfunction "2_2") (pintype "passive"))
      (node (ref "SW83") (pin "2") (pinfunction "2_2") (pintype "passive"))
      (node (ref "SW84") (pin "2") (pinfunction "2_2") (pintype "passive"))
      (node (ref "SW85") (pin "2") (pinfunction "2_2") (pintype "passive"))
      (node (ref "SW86") (pin "2") (pinfunction "2_2") (pintype "passive"))
      (node (ref "SW87") (pin "2") (pinfunction "2_2") (pintype "passive"))
    )
    (net (code "23") (name "/krow6") (class "Default")
      (node (ref "P2") (pin "12") (pinfunction "12_12") (pintype "passive"))
      (node (ref "R16") (pin "1") (pinfunction "1_1") (pintype "passive"))
      (node (ref "SW1") (pin "2") (pinfunction "2_2") (pintype "passive"))
      (node (ref "SW10") (pin "2") (pinfunction "2_2") (pintype "passive"))
      (node (ref "SW11") (pin "2") (pinfunction "2_2") (pintype "passive"))
      (node (ref "SW12") (pin "2") (pinfunction "2_2") (pintype "passive"))
      (node (ref "SW13") (pin "2") (pinfunction "2_2") (pintype "passive"))
      (node (ref "SW14") (pin "2") (pinfunction "2_2") (pintype "passive"))
      (node (ref "SW15") (pin "2") (pinfunction "2_2") (pintype "passive"))
      (node (ref "SW16") (pin "2") (pinfunction "2_2") (pintype "passive"))
      (node (ref "SW16") (pin "3") (pinfunction "3_3") (pintype "passive"))
      (node (ref "SW2") (pin "2") (pinfunction "2_2") (pintype "passive"))
      (node (ref "SW3") (pin "2") (pinfunction "2_2") (pintype "passive"))
      (node (ref "SW32") (pin "3") (pinfunction "3_3") (pintype "passive"))
      (node (ref "SW4") (pin "2") (pinfunction "2_2") (pintype "passive"))
      (node (ref "SW49") (pin "3") (pinfunction "3_3") (pintype "passive"))
      (node (ref "SW5") (pin "2") (pinfunction "2_2") (pintype "passive"))
      (node (ref "SW6") (pin "2") (pinfunction "2_2") (pintype "passive"))
      (node (ref "SW7") (pin "2") (pinfunction "2_2") (pintype "passive"))
      (node (ref "SW76") (pin "3") (pinfunction "3_3") (pintype "passive"))
      (node (ref "SW8") (pin "2") (pinfunction "2_2") (pintype "passive"))
      (node (ref "SW86") (pin "3") (pinfunction "3_3") (pintype "passive"))
      (node (ref "SW9") (pin "2") (pinfunction "2_2") (pintype "passive"))
    )
    (net (code "24") (name "/lrow1") (class "Default")
      (node (ref "P2") (pin "6") (pinfunction "6_6") (pintype "passive"))
      (node (ref "SW17") (pin "4") (pinfunction "4_4") (pintype "passive"))
      (node (ref "SW18") (pin "4") (pinfunction "4_4") (pintype "passive"))
      (node (ref "SW19") (pin "4") (pinfunction "4_4") (pintype "passive"))
      (node (ref "SW20") (pin "4") (pinfunction "4_4") (pintype "passive"))
      (node (ref "SW21") (pin "4") (pinfunction "4_4") (pintype "passive"))
      (node (ref "SW22") (pin "4") (pinfunction "4_4") (pintype "passive"))
      (node (ref "SW23") (pin "4") (pinfunction "4_4") (pintype "passive"))
      (node (ref "SW24") (pin "4") (pinfunction "4_4") (pintype "passive"))
      (node (ref "SW25") (pin "4") (pinfunction "4_4") (pintype "passive"))
      (node (ref "SW26") (pin "4") (pinfunction "4_4") (pintype "passive"))
      (node (ref "SW27") (pin "4") (pinfunction "4_4") (pintype "passive"))
      (node (ref "SW28") (pin "4") (pinfunction "4_4") (pintype "passive"))
      (node (ref "SW29") (pin "4") (pinfunction "4_4") (pintype "passive"))
      (node (ref "SW30") (pin "4") (pinfunction "4_4") (pintype "passive"))
      (node (ref "SW31") (pin "4") (pinfunction "4_4") (pintype "passive"))
      (node (ref "SW32") (pin "4") (pinfunction "4_4") (pintype "passive"))
      (node (ref "SW33") (pin "4") (pinfunction "4_4") (pintype "passive"))
    )
    (net (code "25") (name "/lrow2") (class "Default")
      (node (ref "P2") (pin "7") (pinfunction "7_7") (pintype "passive"))
      (node (ref "SW34") (pin "4") (pinfunction "4_4") (pintype "passive"))
      (node (ref "SW35") (pin "4") (pinfunction "4_4") (pintype "passive"))
      (node (ref "SW36") (pin "4") (pinfunction "4_4") (pintype "passive"))
      (node (ref "SW37") (pin "4") (pinfunction "4_4") (pintype "passive"))
      (node (ref "SW38") (pin "4") (pinfunction "4_4") (pintype "passive"))
      (node (ref "SW39") (pin "4") (pinfunction "4_4") (pintype "passive"))
      (node (ref "SW40") (pin "4") (pinfunction "4_4") (pintype "passive"))
      (node (ref "SW41") (pin "4") (pinfunction "4_4") (pintype "passive"))
      (node (ref "SW42") (pin "4") (pinfunction "4_4") (pintype "passive"))
      (node (ref "SW43") (pin "4") (pinfunction "4_4") (pintype "passive"))
      (node (ref "SW44") (pin "4") (pinfunction "4_4") (pintype "passive"))
      (node (ref "SW45") (pin "4") (pinfunction "4_4") (pintype "passive"))
      (node (ref "SW46") (pin "4") (pinfunction "4_4") (pintype "passive"))
      (node (ref "SW47") (pin "4") (pinfunction "4_4") (pintype "passive"))
      (node (ref "SW48") (pin "4") (pinfunction "4_4") (pintype "passive"))
      (node (ref "SW49") (pin "4") (pinfunction "4_4") (pintype "passive"))
      (node (ref "SW50") (pin "4") (pinfunction "4_4") (pintype "passive"))
    )
    (net (code "26") (name "/lrow4") (class "Default")
      (node (ref "P2") (pin "9") (pinfunction "9_9") (pintype "passive"))
      (node (ref "SW64") (pin "4") (pinfunction "4_4") (pintype "passive"))
      (node (ref "SW65") (pin "4") (pinfunction "4_4") (pintype "passive"))
      (node (ref "SW66") (pin "4") (pinfunction "4_4") (pintype "passive"))
      (node (ref "SW67") (pin "4") (pinfunction "4_4") (pintype "passive"))
      (node (ref "SW68") (pin "4") (pinfunction "4_4") (pintype "passive"))
      (node (ref "SW69") (pin "4") (pinfunction "4_4") (pintype "passive"))
      (node (ref "SW70") (pin "4") (pinfunction "4_4") (pintype "passive"))
      (node (ref "SW71") (pin "4") (pinfunction "4_4") (pintype "passive"))
      (node (ref "SW72") (pin "4") (pinfunction "4_4") (pintype "passive"))
      (node (ref "SW73") (pin "4") (pinfunction "4_4") (pintype "passive"))
      (node (ref "SW74") (pin "4") (pinfunction "4_4") (pintype "passive"))
      (node (ref "SW75") (pin "4") (pinfunction "4_4") (pintype "passive"))
      (node (ref "SW76") (pin "4") (pinfunction "4_4") (pintype "passive"))
    )
    (net (code "27") (name "/lrow5") (class "Default")
      (node (ref "P2") (pin "10") (pinfunction "10_10") (pintype "passive"))
      (node (ref "SW77") (pin "4") (pinfunction "4_4") (pintype "passive"))
      (node (ref "SW78") (pin "4") (pinfunction "4_4") (pintype "passive"))
      (node (ref "SW79") (pin "4") (pinfunction "4_4") (pintype "passive"))
      (node (ref "SW80") (pin "4") (pinfunction "4_4") (pintype "passive"))
      (node (ref "SW81") (pin "4") (pinfunction "4_4") (pintype "passive"))
      (node (ref "SW82") (pin "4") (pinfunction "4_4") (pintype "passive"))
      (node (ref "SW83") (pin "4") (pinfunction "4_4") (pintype "passive"))
      (node (ref "SW84") (pin "4") (pinfunction "4_4") (pintype "passive"))
      (node (ref "SW85") (pin "4") (pinfunction "4_4") (pintype "passive"))
      (node (ref "SW86") (pin "4") (pinfunction "4_4") (pintype "passive"))
      (node (ref "SW87") (pin "4") (pinfunction "4_4") (pintype "passive"))
    )
    (net (code "28") (name "/lrow6") (class "Default")
      (node (ref "P2") (pin "11") (pinfunction "11_11") (pintype "passive"))
      (node (ref "SW1") (pin "4") (pinfunction "4_4") (pintype "passive"))
      (node (ref "SW10") (pin "4") (pinfunction "4_4") (pintype "passive"))
      (node (ref "SW11") (pin "4") (pinfunction "4_4") (pintype "passive"))
      (node (ref "SW12") (pin "4") (pinfunction "4_4") (pintype "passive"))
      (node (ref "SW13") (pin "4") (pinfunction "4_4") (pintype "passive"))
      (node (ref "SW14") (pin "4") (pinfunction "4_4") (pintype "passive"))
      (node (ref "SW15") (pin "4") (pinfunction "4_4") (pintype "passive"))
      (node (ref "SW16") (pin "4") (pinfunction "4_4") (pintype "passive"))
      (node (ref "SW2") (pin "4") (pinfunction "4_4") (pintype "passive"))
      (node (ref "SW3") (pin "4") (pinfunction "4_4") (pintype "passive"))
      (node (ref "SW4") (pin "4") (pinfunction "4_4") (pintype "passive"))
      (node (ref "SW5") (pin "4") (pinfunction "4_4") (pintype "passive"))
      (node (ref "SW6") (pin "4") (pinfunction "4_4") (pintype "passive"))
      (node (ref "SW7") (pin "4") (pinfunction "4_4") (pintype "passive"))
      (node (ref "SW8") (pin "4") (pinfunction "4_4") (pintype "passive"))
      (node (ref "SW9") (pin "4") (pinfunction "4_4") (pintype "passive"))
    )
    (net (code "29") (name "GND") (class "Default")
      (node (ref "P1") (pin "17") (pinfunction "17_17") (pintype "passive"))
    )
    (net (code "30") (name "Net-(R1-Pad1)") (class "Default")
      (node (ref "R1") (pin "1") (pinfunction "1_1") (pintype "passive"))
      (node (ref "SW17") (pin "3") (pinfunction "3_3") (pintype "passive"))
      (node (ref "SW2") (pin "3") (pinfunction "3_3") (pintype "passive"))
      (node (ref "SW34") (pin "3") (pinfunction "3_3") (pintype "passive"))
      (node (ref "SW51") (pin "3") (pinfunction "3_3") (pintype "passive"))
      (node (ref "SW64") (pin "3") (pinfunction "3_3") (pintype "passive"))
      (node (ref "SW77") (pin "3") (pinfunction "3_3") (pintype "passive"))
    )
    (net (code "31") (name "Net-(R2-Pad1)") (class "Default")
      (node (ref "R2") (pin "1") (pinfunction "1_1") (pintype "passive"))
      (node (ref "SW18") (pin "3") (pinfunction "3_3") (pintype "passive"))
      (node (ref "SW3") (pin "3") (pinfunction "3_3") (pintype "passive"))
      (node (ref "SW35") (pin "3") (pinfunction "3_3") (pintype "passive"))
      (node (ref "SW52") (pin "3") (pinfunction "3_3") (pintype "passive"))
      (node (ref "SW78") (pin "3") (pinfunction "3_3") (pintype "passive"))
    )
    (net (code "32") (name "Net-(R3-Pad1)") (class "Default")
      (node (ref "R3") (pin "1") (pinfunction "1_1") (pintype "passive"))
      (node (ref "SW19") (pin "3") (pinfunction "3_3") (pintype "passive"))
      (node (ref "SW36") (pin "3") (pinfunction "3_3") (pintype "passive"))
      (node (ref "SW4") (pin "3") (pinfunction "3_3") (pintype "passive"))
      (node (ref "SW53") (pin "3") (pinfunction "3_3") (pintype "passive"))
      (node (ref "SW65") (pin "3") (pinfunction "3_3") (pintype "passive"))
      (node (ref "SW79") (pin "3") (pinfunction "3_3") (pintype "passive"))
    )
    (net (code "33") (name "Net-(R4-Pad1)") (class "Default")
      (node (ref "R4") (pin "1") (pinfunction "1_1") (pintype "passive"))
      (node (ref "SW20") (pin "3") (pinfunction "3_3") (pintype "passive"))
      (node (ref "SW37") (pin "3") (pinfunction "3_3") (pintype "passive"))
      (node (ref "SW5") (pin "3") (pinfunction "3_3") (pintype "passive"))
      (node (ref "SW54") (pin "3") (pinfunction "3_3") (pintype "passive"))
      (node (ref "SW66") (pin "3") (pinfunction "3_3") (pintype "passive"))
    )
    (net (code "34") (name "Net-(R5-Pad1)") (class "Default")
      (node (ref "R5") (pin "1") (pinfunction "1_1") (pintype "passive"))
      (node (ref "SW21") (pin "3") (pinfunction "3_3") (pintype "passive"))
      (node (ref "SW38") (pin "3") (pinfunction "3_3") (pintype "passive"))
      (node (ref "SW55") (pin "3") (pinfunction "3_3") (pintype "passive"))
      (node (ref "SW6") (pin "3") (pinfunction "3_3") (pintype "passive"))
      (node (ref "SW67") (pin "3") (pinfunction "3_3") (pintype "passive"))
    )
    (net (code "35") (name "Net-(R6-Pad1)") (class "Default")
      (node (ref "R6") (pin "1") (pinfunction "1_1") (pintype "passive"))
      (node (ref "SW22") (pin "3") (pinfunction "3_3") (pintype "passive"))
      (node (ref "SW39") (pin "3") (pinfunction "3_3") (pintype "passive"))
      (node (ref "SW56") (pin "3") (pinfunction "3_3") (pintype "passive"))
      (node (ref "SW68") (pin "3") (pinfunction "3_3") (pintype "passive"))
      (node (ref "SW7") (pin "3") (pinfunction "3_3") (pintype "passive"))
    )
    (net (code "36") (name "Net-(R7-Pad1)") (class "Default")
      (node (ref "R7") (pin "1") (pinfunction "1_1") (pintype "passive"))
      (node (ref "SW23") (pin "3") (pinfunction "3_3") (pintype "passive"))
      (node (ref "SW40") (pin "3") (pinfunction "3_3") (pintype "passive"))
      (node (ref "SW57") (pin "3") (pinfunction "3_3") (pintype "passive"))
      (node (ref "SW69") (pin "3") (pinfunction "3_3") (pintype "passive"))
      (node (ref "SW8") (pin "3") (pinfunction "3_3") (pintype "passive"))
      (node (ref "SW80") (pin "3") (pinfunction "3_3") (pintype "passive"))
    )
    (net (code "37") (name "Net-(R8-Pad1)") (class "Default")
      (node (ref "R8") (pin "1") (pinfunction "1_1") (pintype "passive"))
      (node (ref "SW24") (pin "3") (pinfunction "3_3") (pintype "passive"))
      (node (ref "SW41") (pin "3") (pinfunction "3_3") (pintype "passive"))
      (node (ref "SW58") (pin "3") (pinfunction "3_3") (pintype "passive"))
      (node (ref "SW70") (pin "3") (pinfunction "3_3") (pintype "passive"))
      (node (ref "SW9") (pin "3") (pinfunction "3_3") (pintype "passive"))
    )
    (net (code "38") (name "Net-(R9-Pad1)") (class "Default")
      (node (ref "R9") (pin "1") (pinfunction "1_1") (pintype "passive"))
      (node (ref "SW10") (pin "3") (pinfunction "3_3") (pintype "passive"))
      (node (ref "SW25") (pin "3") (pinfunction "3_3") (pintype "passive"))
      (node (ref "SW42") (pin "3") (pinfunction "3_3") (pintype "passive"))
      (node (ref "SW59") (pin "3") (pinfunction "3_3") (pintype "passive"))
      (node (ref "SW71") (pin "3") (pinfunction "3_3") (pintype "passive"))
    )
    (net (code "39") (name "Net-(R10-Pad1)") (class "Default")
      (node (ref "R10") (pin "1") (pinfunction "1_1") (pintype "passive"))
      (node (ref "SW26") (pin "3") (pinfunction "3_3") (pintype "passive"))
      (node (ref "SW43") (pin "3") (pinfunction "3_3") (pintype "passive"))
      (node (ref "SW60") (pin "3") (pinfunction "3_3") (pintype "passive"))
      (node (ref "SW72") (pin "3") (pinfunction "3_3") (pintype "passive"))
    )
    (net (code "40") (name "Net-(R11-Pad1)") (class "Default")
      (node (ref "R11") (pin "1") (pinfunction "1_1") (pintype "passive"))
      (node (ref "SW11") (pin "3") (pinfunction "3_3") (pintype "passive"))
      (node (ref "SW27") (pin "3") (pinfunction "3_3") (pintype "passive"))
      (node (ref "SW44") (pin "3") (pinfunction "3_3") (pintype "passive"))
      (node (ref "SW61") (pin "3") (pinfunction "3_3") (pintype "passive"))
      (node (ref "SW73") (pin "3") (pinfunction "3_3") (pintype "passive"))
      (node (ref "SW81") (pin "3") (pinfunction "3_3") (pintype "passive"))
    )
    (net (code "41") (name "Net-(R12-Pad1)") (class "Default")
      (node (ref "R12") (pin "1") (pinfunction "1_1") (pintype "passive"))
      (node (ref "SW12") (pin "3") (pinfunction "3_3") (pintype "passive"))
      (node (ref "SW28") (pin "3") (pinfunction "3_3") (pintype "passive"))
      (node (ref "SW45") (pin "3") (pinfunction "3_3") (pintype "passive"))
      (node (ref "SW62") (pin "3") (pinfunction "3_3") (pintype "passive"))
      (node (ref "SW74") (pin "3") (pinfunction "3_3") (pintype "passive"))
      (node (ref "SW82") (pin "3") (pinfunction "3_3") (pintype "passive"))
    )
    (net (code "42") (name "Net-(R13-Pad1)") (class "Default")
      (node (ref "R13") (pin "1") (pinfunction "1_1") (pintype "passive"))
      (node (ref "SW13") (pin "3") (pinfunction "3_3") (pintype "passive"))
      (node (ref "SW29") (pin "3") (pinfunction "3_3") (pintype "passive"))
      (node (ref "SW46") (pin "3") (pinfunction "3_3") (pintype "passive"))
      (node (ref "SW83") (pin "3") (pinfunction "3_3") (pintype "passive"))
    )
    (net (code "43") (name "Net-(R14-Pad1)") (class "Default")
      (node (ref "R14") (pin "1") (pinfunction "1_1") (pintype "passive"))
      (node (ref "SW14") (pin "3") (pinfunction "3_3") (pintype "passive"))
      (node (ref "SW30") (pin "3") (pinfunction "3_3") (pintype "passive"))
      (node (ref "SW47") (pin "3") (pinfunction "3_3") (pintype "passive"))
      (node (ref "SW63") (pin "3") (pinfunction "3_3") (pintype "passive"))
      (node (ref "SW75") (pin "3") (pinfunction "3_3") (pintype "passive"))
      (node (ref "SW84") (pin "3") (pinfunction "3_3") (pintype "passive"))
    )
    (net (code "44") (name "Net-(R15-Pad1)") (class "Default")
      (node (ref "R15") (pin "1") (pinfunction "1_1") (pintype "passive"))
      (node (ref "SW15") (pin "3") (pinfunction "3_3") (pintype "passive"))
      (node (ref "SW31") (pin "3") (pinfunction "3_3") (pintype "passive"))
      (node (ref "SW48") (pin "3") (pinfunction "3_3") (pintype "passive"))
      (node (ref "SW85") (pin "3") (pinfunction "3_3") (pintype "passive"))
    )
    (net (code "45") (name "Net-(R17-Pad1)") (class "Default")
      (node (ref "R17") (pin "1") (pinfunction "1_1") (pintype "passive"))
      (node (ref "SW1") (pin "3") (pinfunction "3_3") (pintype "passive"))
      (node (ref "SW33") (pin "3") (pinfunction "3_3") (pintype "passive"))
      (node (ref "SW50") (pin "3") (pinfunction "3_3") (pintype "passive"))
      (node (ref "SW87") (pin "3") (pinfunction "3_3") (pintype "passive"))
    )
    (net (code "46") (name "VCC") (class "Default")
      (node (ref "P2") (pin "17") (pinfunction "17_17") (pintype "passive"))
      (node (ref "R1") (pin "2") (pinfunction "2_2") (pintype "passive"))
      (node (ref "R10") (pin "2") (pinfunction "2_2") (pintype "passive"))
      (node (ref "R11") (pin "2") (pinfunction "2_2") (pintype "passive"))
      (node (ref "R12") (pin "2") (pinfunction "2_2") (pintype "passive"))
      (node (ref "R13") (pin "2") (pinfunction "2_2") (pintype "passive"))
      (node (ref "R14") (pin "2") (pinfunction "2_2") (pintype "passive"))
      (node (ref "R15") (pin "2") (pinfunction "2_2") (pintype "passive"))
      (node (ref "R16") (pin "2") (pinfunction "2_2") (pintype "passive"))
      (node (ref "R17") (pin "2") (pinfunction "2_2") (pintype "passive"))
      (node (ref "R2") (pin "2") (pinfunction "2_2") (pintype "passive"))
      (node (ref "R3") (pin "2") (pinfunction "2_2") (pintype "passive"))
      (node (ref "R4") (pin "2") (pinfunction "2_2") (pintype "passive"))
      (node (ref "R5") (pin "2") (pinfunction "2_2") (pintype "passive"))
      (node (ref "R6") (pin "2") (pinfunction "2_2") (pintype "passive"))
      (node (ref "R7") (pin "2") (pinfunction "2_2") (pintype "passive"))
      (node (ref "R8") (pin "2") (pinfunction "2_2") (pintype "passive"))
      (node (ref "R9") (pin "2") (pinfunction "2_2") (pintype "passive"))
    )
    (net (code "47") (name "unconnected-(P2-Pad13)") (class "Default")
      (node (ref "P2") (pin "13") (pinfunction "13_13") (pintype "passive"))
    )
    (net (code "48") (name "unconnected-(P2-Pad14)") (class "Default")
      (node (ref "P2") (pin "14") (pinfunction "14_14") (pintype "passive"))
    )
    (net (code "49") (name "unconnected-(P2-Pad15)") (class "Default")
      (node (ref "P2") (pin "15") (pinfunction "15_15") (pintype "passive"))
    )
  )
)
